# LEDtestBoard.net
KiCad netlist of a schematic drawn in EAGLE
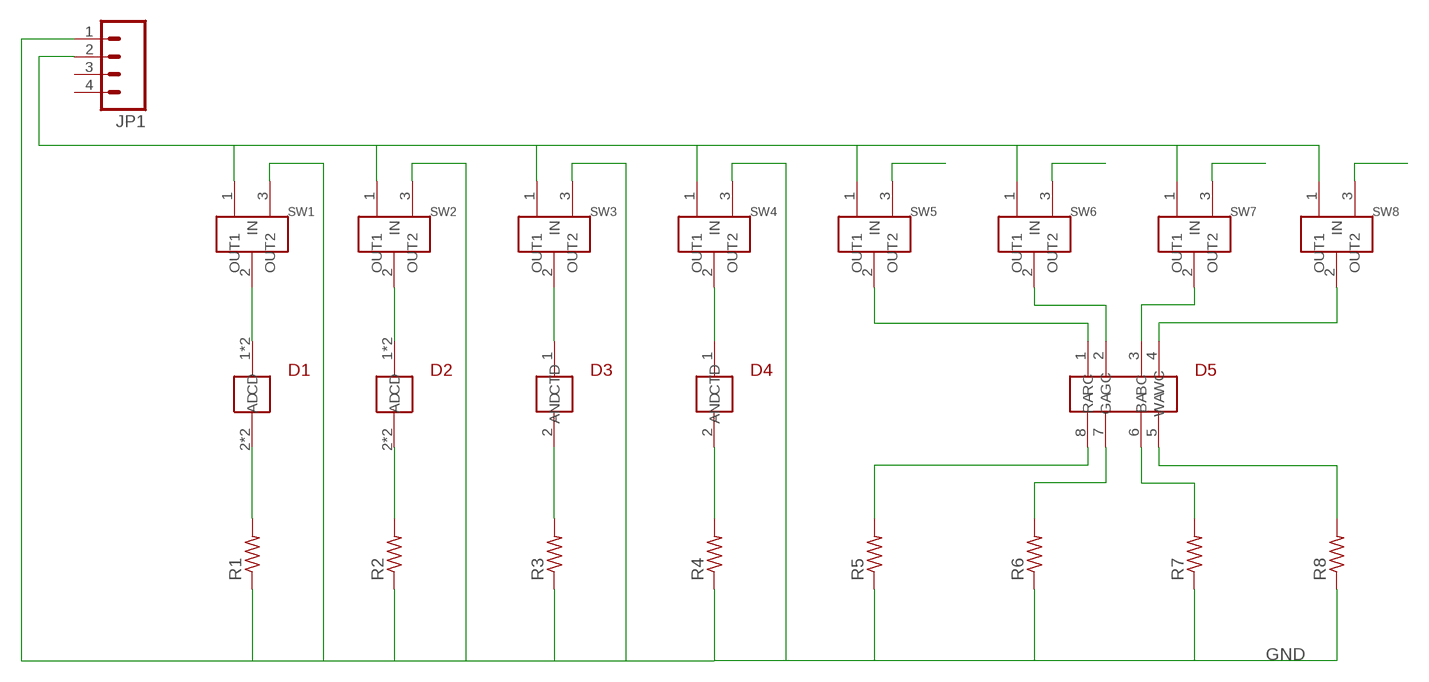
[diagram p0: schematic, sheet 1]

(export (version "E")
  (design (tool "Eeschema 10.0.6"))
  (components
    (comp (ref "D1")
      (value "SZA05A0A")
      (footprint "eagle-import:SZA05A0A")
      (libsource (lib "eagle-import") (part "SZA05A0A"))
    )
    (comp (ref "D2")
      (value "SZA05A0A")
      (footprint "eagle-import:SZA05A0A")
      (libsource (lib "eagle-import") (part "SZA05A0A"))
    )
    (comp (ref "D3")
      (value "LACN5MFBGB241Z")
      (footprint "eagle-import:2-SMD-LED-NO-EXP")
      (libsource (lib "eagle-import") (part "LACN5MFBGB241Z"))
    )
    (comp (ref "D4")
      (value "LACN5MFBGB241Z")
      (footprint "eagle-import:2-SMD-LED-NO-EXP")
      (libsource (lib "eagle-import") (part "LACN5MFBGB241Z"))
    )
    (comp (ref "D5")
      (value "XLAMP_COLOR")
      (footprint "eagle-import:8-SMD-LED")
      (libsource (lib "eagle-import") (part "XLAMP_COLOR"))
    )
    (comp (ref "JP1")
      (value "M04PTH")
      (footprint "eagle-import:1X04")
      (libsource (lib "eagle-import") (part "M04PTH"))
    )
    (comp (ref "R1")
      (value "R-US_R0603")
      (footprint "eagle-import:R0603")
      (libsource (lib "eagle-import") (part "R-US_R0603"))
    )
    (comp (ref "R2")
      (value "R-US_R0603")
      (footprint "eagle-import:R0603")
      (libsource (lib "eagle-import") (part "R-US_R0603"))
    )
    (comp (ref "R3")
      (value "R-US_R0603")
      (footprint "eagle-import:R0603")
      (libsource (lib "eagle-import") (part "R-US_R0603"))
    )
    (comp (ref "R4")
      (value "R-US_R0603")
      (footprint "eagle-import:R0603")
      (libsource (lib "eagle-import") (part "R-US_R0603"))
    )
    (comp (ref "R5")
      (value "R-US_R0603")
      (footprint "eagle-import:R0603")
      (libsource (lib "eagle-import") (part "R-US_R0603"))
    )
    (comp (ref "R6")
      (value "R-US_R0603")
      (footprint "eagle-import:R0603")
      (libsource (lib "eagle-import") (part "R-US_R0603"))
    )
    (comp (ref "R7")
      (value "R-US_R0603")
      (footprint "eagle-import:R0603")
      (libsource (lib "eagle-import") (part "R-US_R0603"))
    )
    (comp (ref "R8")
      (value "R-US_R0603")
      (footprint "eagle-import:R0603")
      (libsource (lib "eagle-import") (part "R-US_R0603"))
    )
    (comp (ref "SW1")
      (value "PCM12SMTR")
      (footprint "eagle-import:PCM12SMTR")
      (libsource (lib "eagle-import") (part "PCM12SMTR"))
    )
    (comp (ref "SW2")
      (value "PCM12SMTR")
      (footprint "eagle-import:PCM12SMTR")
      (libsource (lib "eagle-import") (part "PCM12SMTR"))
    )
    (comp (ref "SW3")
      (value "PCM12SMTR")
      (footprint "eagle-import:PCM12SMTR")
      (libsource (lib "eagle-import") (part "PCM12SMTR"))
    )
    (comp (ref "SW4")
      (value "PCM12SMTR")
      (footprint "eagle-import:PCM12SMTR")
      (libsource (lib "eagle-import") (part "PCM12SMTR"))
    )
    (comp (ref "SW5")
      (value "PCM12SMTR")
      (footprint "eagle-import:PCM12SMTR")
      (libsource (lib "eagle-import") (part "PCM12SMTR"))
    )
    (comp (ref "SW6")
      (value "PCM12SMTR")
      (footprint "eagle-import:PCM12SMTR")
      (libsource (lib "eagle-import") (part "PCM12SMTR"))
    )
    (comp (ref "SW7")
      (value "PCM12SMTR")
      (footprint "eagle-import:PCM12SMTR")
      (libsource (lib "eagle-import") (part "PCM12SMTR"))
    )
    (comp (ref "SW8")
      (value "PCM12SMTR")
      (footprint "eagle-import:PCM12SMTR")
      (libsource (lib "eagle-import") (part "PCM12SMTR"))
    )
  )
  (nets
    (net (code "1") (name "/GND") (class "Default")
      (node (ref "JP1") (pin "1") (pinfunction "1_1") (pintype "passive"))
      (node (ref "R1") (pin "1") (pinfunction "1_1") (pintype "passive"))
      (node (ref "R2") (pin "1") (pinfunction "1_1") (pintype "passive"))
      (node (ref "R3") (pin "1") (pinfunction "1_1") (pintype "passive"))
      (node (ref "R4") (pin "1") (pinfunction "1_1") (pintype "passive"))
      (node (ref "R5") (pin "1") (pinfunction "1_1") (pintype "passive"))
      (node (ref "R6") (pin "1") (pinfunction "1_1") (pintype "passive"))
      (node (ref "R7") (pin "1") (pinfunction "1_1") (pintype "passive"))
      (node (ref "R8") (pin "1") (pinfunction "1_1") (pintype "passive"))
      (node (ref "SW1") (pin "3") (pinfunction "OUT2_3") (pintype "bidirectional"))
      (node (ref "SW2") (pin "3") (pinfunction "OUT2_3") (pintype "bidirectional"))
      (node (ref "SW3") (pin "3") (pinfunction "OUT2_3") (pintype "bidirectional"))
      (node (ref "SW4") (pin "3") (pinfunction "OUT2_3") (pintype "bidirectional"))
      (node (ref "SW5") (pin "3") (pinfunction "OUT2_3") (pintype "bidirectional"))
      (node (ref "SW6") (pin "3") (pinfunction "OUT2_3") (pintype "bidirectional"))
      (node (ref "SW7") (pin "3") (pinfunction "OUT2_3") (pintype "bidirectional"))
      (node (ref "SW8") (pin "3") (pinfunction "OUT2_3") (pintype "bidirectional"))
    )
    (net (code "2") (name "Net-(D1-CD-Pad12)") (class "Default")
      (node (ref "D1") (pin "12") (pinfunction "CD_12") (pintype "bidirectional"))
      (node (ref "D1") (pin "2") (pinfunction "CD_2") (pintype "bidirectional"))
      (node (ref "R1") (pin "2") (pinfunction "2_2") (pintype "passive"))
    )
    (net (code "3") (name "Net-(D2-CD-Pad12)") (class "Default")
      (node (ref "D2") (pin "12") (pinfunction "CD_12") (pintype "bidirectional"))
      (node (ref "D2") (pin "2") (pinfunction "CD_2") (pintype "bidirectional"))
      (node (ref "R2") (pin "2") (pinfunction "2_2") (pintype "passive"))
    )
    (net (code "4") (name "Net-(D3-AND)") (class "Default")
      (node (ref "D3") (pin "1") (pinfunction "AND_1") (pintype "bidirectional"))
      (node (ref "SW3") (pin "2") (pinfunction "IN_2") (pintype "bidirectional"))
    )
    (net (code "5") (name "Net-(D3-CTD)") (class "Default")
      (node (ref "D3") (pin "2") (pinfunction "CTD_2") (pintype "bidirectional"))
      (node (ref "R3") (pin "2") (pinfunction "2_2") (pintype "passive"))
    )
    (net (code "6") (name "Net-(D4-AND)") (class "Default")
      (node (ref "D4") (pin "1") (pinfunction "AND_1") (pintype "bidirectional"))
      (node (ref "SW4") (pin "2") (pinfunction "IN_2") (pintype "bidirectional"))
    )
    (net (code "7") (name "Net-(D4-CTD)") (class "Default")
      (node (ref "D4") (pin "2") (pinfunction "CTD_2") (pintype "bidirectional"))
      (node (ref "R4") (pin "2") (pinfunction "2_2") (pintype "passive"))
    )
    (net (code "8") (name "Net-(D5-BA)") (class "Default")
      (node (ref "D5") (pin "3") (pinfunction "BA_3") (pintype "bidirectional"))
      (node (ref "SW7") (pin "2") (pinfunction "IN_2") (pintype "bidirectional"))
    )
    (net (code "9") (name "Net-(D5-BC)") (class "Default")
      (node (ref "D5") (pin "6") (pinfunction "BC_6") (pintype "bidirectional"))
      (node (ref "R7") (pin "2") (pinfunction "2_2") (pintype "passive"))
    )
    (net (code "10") (name "Net-(D5-GA)") (class "Default")
      (node (ref "D5") (pin "2") (pinfunction "GA_2") (pintype "bidirectional"))
      (node (ref "SW6") (pin "2") (pinfunction "IN_2") (pintype "bidirectional"))
    )
    (net (code "11") (name "Net-(D5-GC)") (class "Default")
      (node (ref "D5") (pin "7") (pinfunction "GC_7") (pintype "bidirectional"))
      (node (ref "R6") (pin "2") (pinfunction "2_2") (pintype "passive"))
    )
    (net (code "12") (name "Net-(D5-RA)") (class "Default")
      (node (ref "D5") (pin "1") (pinfunction "RA_1") (pintype "bidirectional"))
      (node (ref "SW5") (pin "2") (pinfunction "IN_2") (pintype "bidirectional"))
    )
    (net (code "13") (name "Net-(D5-RC)") (class "Default")
      (node (ref "D5") (pin "8") (pinfunction "RC_8") (pintype "bidirectional"))
      (node (ref "R5") (pin "2") (pinfunction "2_2") (pintype "passive"))
    )
    (net (code "14") (name "Net-(D5-WA)") (class "Default")
      (node (ref "D5") (pin "4") (pinfunction "WA_4") (pintype "bidirectional"))
      (node (ref "SW8") (pin "2") (pinfunction "IN_2") (pintype "bidirectional"))
    )
    (net (code "15") (name "Net-(D5-WC)") (class "Default")
      (node (ref "D5") (pin "5") (pinfunction "WC_5") (pintype "bidirectional"))
      (node (ref "R8") (pin "2") (pinfunction "2_2") (pintype "passive"))
    )
    (net (code "16") (name "Net-(SW1-IN)") (class "Default")
      (node (ref "D1") (pin "1") (pinfunction "AD_1") (pintype "bidirectional"))
      (node (ref "D1") (pin "11") (pinfunction "AD_11") (pintype "bidirectional"))
      (node (ref "SW1") (pin "2") (pinfunction "IN_2") (pintype "bidirectional"))
    )
    (net (code "17") (name "Net-(SW1-OUT1)") (class "Default")
      (node (ref "JP1") (pin "2") (pinfunction "2_2") (pintype "passive"))
      (node (ref "SW1") (pin "1") (pinfunction "OUT1_1") (pintype "bidirectional"))
      (node (ref "SW2") (pin "1") (pinfunction "OUT1_1") (pintype "bidirectional"))
      (node (ref "SW3") (pin "1") (pinfunction "OUT1_1") (pintype "bidirectional"))
      (node (ref "SW4") (pin "1") (pinfunction "OUT1_1") (pintype "bidirectional"))
      (node (ref "SW5") (pin "1") (pinfunction "OUT1_1") (pintype "bidirectional"))
      (node (ref "SW6") (pin "1") (pinfunction "OUT1_1") (pintype "bidirectional"))
      (node (ref "SW7") (pin "1") (pinfunction "OUT1_1") (pintype "bidirectional"))
      (node (ref "SW8") (pin "1") (pinfunction "OUT1_1") (pintype "bidirectional"))
    )
    (net (code "18") (name "Net-(SW2-IN)") (class "Default")
      (node (ref "D2") (pin "1") (pinfunction "AD_1") (pintype "bidirectional"))
      (node (ref "D2") (pin "11") (pinfunction "AD_11") (pintype "bidirectional"))
      (node (ref "SW2") (pin "2") (pinfunction "IN_2") (pintype "bidirectional"))
    )
    (net (code "19") (name "unconnected-(JP1-Pad3)") (class "Default")
      (node (ref "JP1") (pin "3") (pinfunction "3_3") (pintype "passive"))
    )
    (net (code "20") (name "unconnected-(JP1-Pad4)") (class "Default")
      (node (ref "JP1") (pin "4") (pinfunction "4_4") (pintype "passive"))
    )
  )
)
